# fretscanner5000.net
KiCad netlist of a schematic drawn in EAGLE
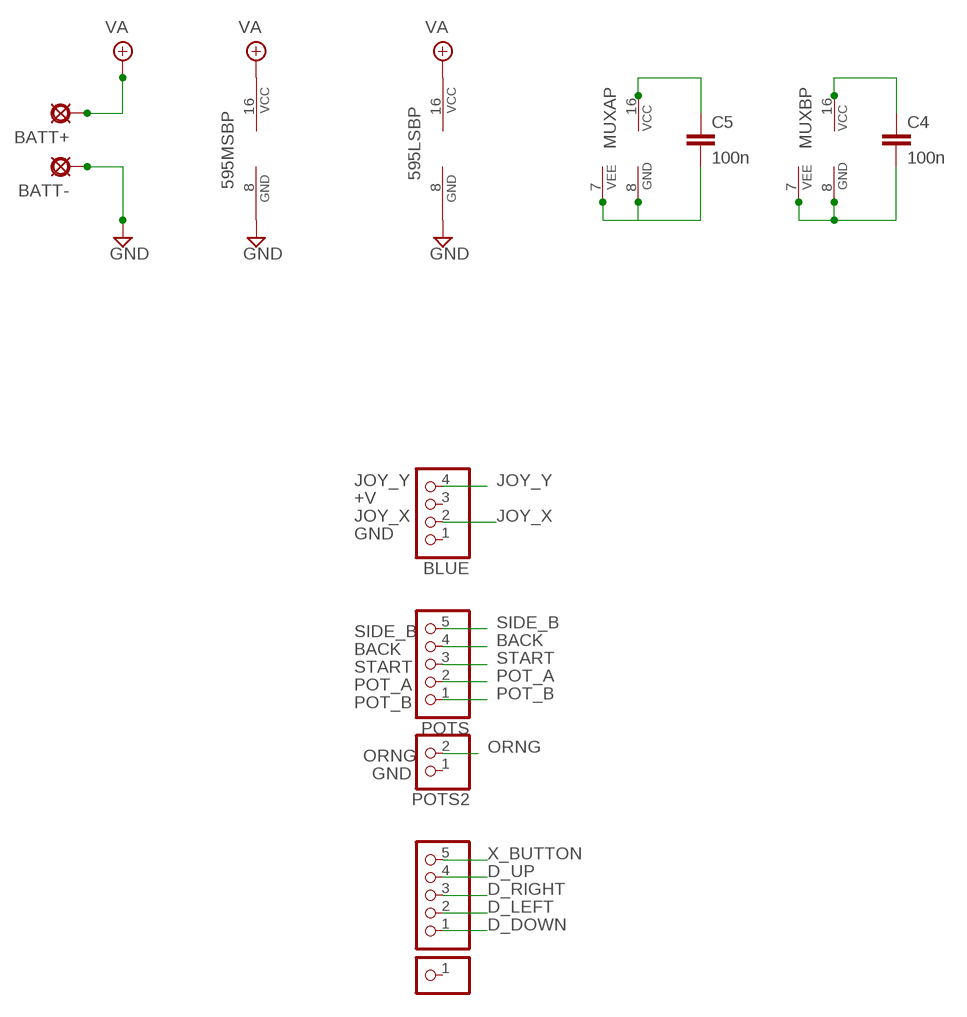
[diagram p0: schematic, sheet 1, part 1 of 2]
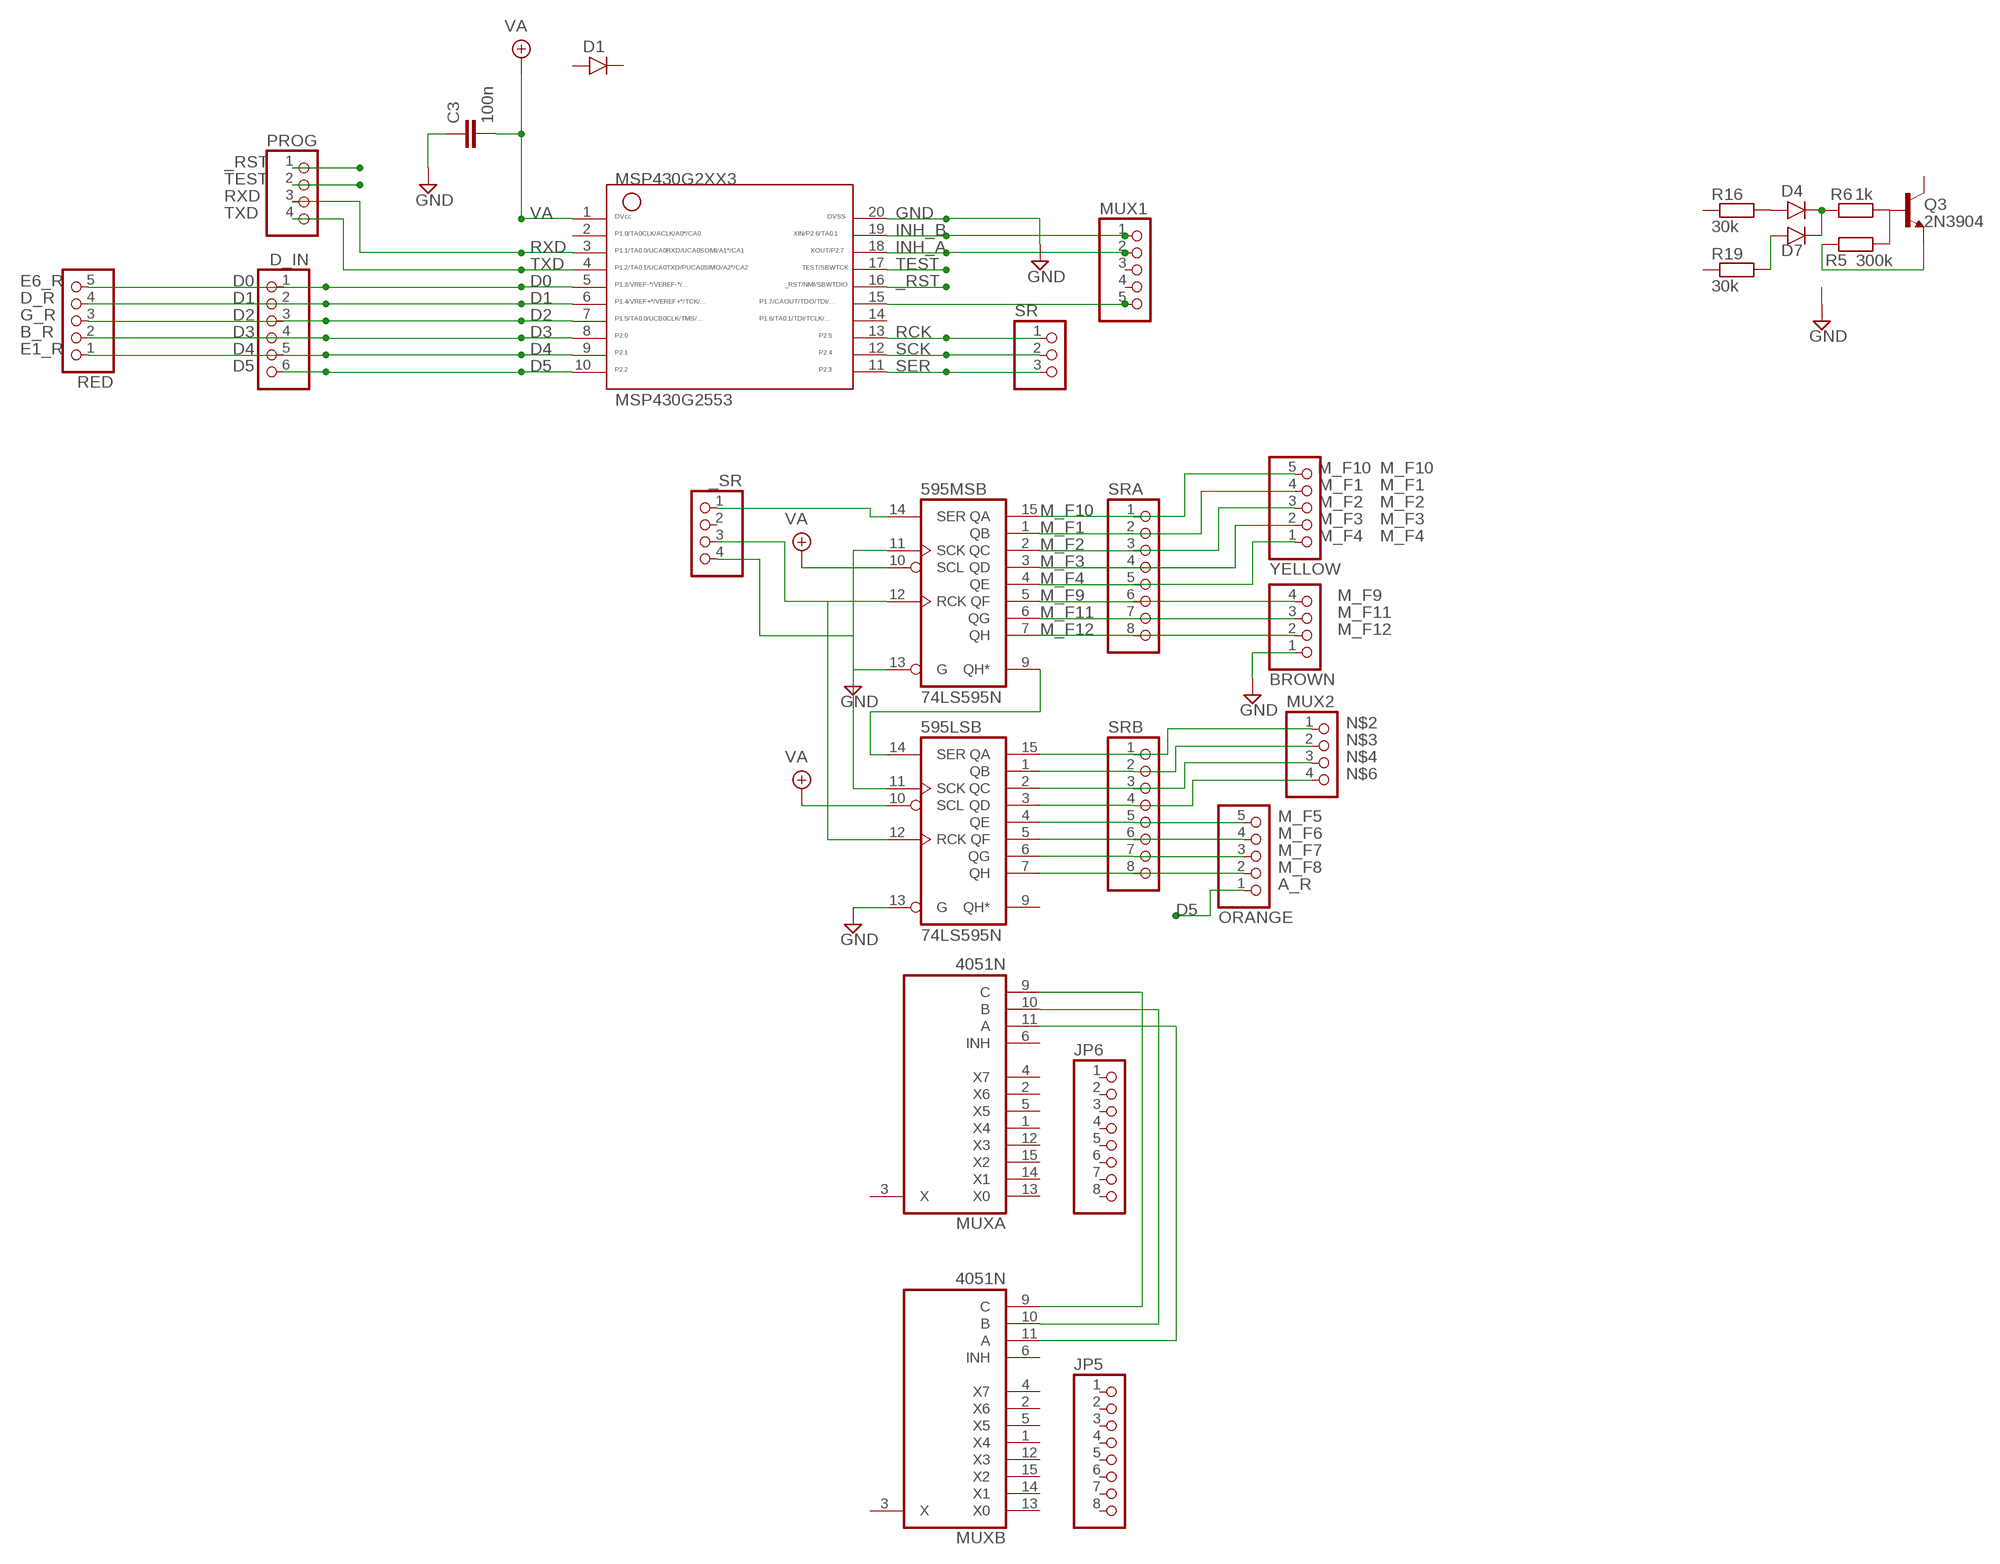
[diagram p1: schematic, sheet 1, part 2 of 2]

(export (version "E")
  (design (tool "Eeschema 10.0.6"))
  (components
    (comp (ref "595LSB")
      (value "74LS595N")
      (footprint "eagle-import:DIL16")
      (libsource (lib "eagle-import") (part "74595NLS"))
    )
    (comp (ref "595MSB")
      (value "74LS595N")
      (footprint "eagle-import:DIL16")
      (libsource (lib "eagle-import") (part "74595NLS"))
    )
    (comp (ref "BATT+")
      (value "PADL")
      (footprint "eagle-import:LONG")
      (libsource (lib "eagle-import") (part "PADL"))
    )
    (comp (ref "BATT-")
      (value "PADL")
      (footprint "eagle-import:LONG")
      (libsource (lib "eagle-import") (part "PADL"))
    )
    (comp (ref "BLUE")
      (value "PINHD-1X4")
      (footprint "eagle-import:1X04")
      (libsource (lib "eagle-import") (part "PINHD-1X4"))
    )
    (comp (ref "BROWN")
      (value "PINHD-1X4")
      (footprint "eagle-import:1X04")
      (libsource (lib "eagle-import") (part "PINHD-1X4"))
    )
    (comp (ref "C3")
      (value "100n")
      (footprint "eagle-import:050X030_050_3")
      (libsource (lib "eagle-import") (part "050X030_050"))
    )
    (comp (ref "C4")
      (value "100n")
      (footprint "eagle-import:050X030_050_3")
      (libsource (lib "eagle-import") (part "050X030_050"))
    )
    (comp (ref "C5")
      (value "100n")
      (footprint "eagle-import:050X030_050_3")
      (libsource (lib "eagle-import") (part "050X030_050"))
    )
    (comp (ref "D1")
      (value "1N400X.4")
      (footprint "eagle-import:DO41-4")
      (libsource (lib "eagle-import") (part "1N400X.4"))
    )
    (comp (ref "D4")
      (value "1N4148-2")
      (footprint "eagle-import:DO35-2")
      (libsource (lib "eagle-import") (part "1N4148-2"))
    )
    (comp (ref "D7")
      (value "1N4148-2")
      (footprint "eagle-import:DO35-2")
      (libsource (lib "eagle-import") (part "1N4148-2"))
    )
    (comp (ref "DPAD")
      (value "PINHD-1X5")
      (footprint "eagle-import:1X05")
      (libsource (lib "eagle-import") (part "PINHD-1X5"))
    )
    (comp (ref "DPAD2")
      (value "PINHD-1X1")
      (footprint "eagle-import:1X01")
      (libsource (lib "eagle-import") (part "PINHD-1X1"))
    )
    (comp (ref "D_IN")
      (value "PINHD-1X6")
      (footprint "eagle-import:1X06")
      (libsource (lib "eagle-import") (part "PINHD-1X6"))
    )
    (comp (ref "JP5")
      (value "PINHD-1X8")
      (footprint "eagle-import:1X08")
      (libsource (lib "eagle-import") (part "PINHD-1X8"))
    )
    (comp (ref "JP6")
      (value "PINHD-1X8")
      (footprint "eagle-import:1X08")
      (libsource (lib "eagle-import") (part "PINHD-1X8"))
    )
    (comp (ref "MSP430G2553")
      (value "G2XX3---N20")
      (footprint "eagle-import:N20")
      (libsource (lib "eagle-import") (part "G2XX3---N20"))
    )
    (comp (ref "MUX1")
      (value "PINHD-1X5")
      (footprint "eagle-import:1X05")
      (libsource (lib "eagle-import") (part "PINHD-1X5"))
    )
    (comp (ref "MUX2")
      (value "PINHD-1X4")
      (footprint "eagle-import:1X04")
      (libsource (lib "eagle-import") (part "PINHD-1X4"))
    )
    (comp (ref "MUXA")
      (value "4051N")
      (footprint "eagle-import:DIL16")
      (libsource (lib "eagle-import") (part "4051N"))
    )
    (comp (ref "MUXB")
      (value "4051N")
      (footprint "eagle-import:DIL16")
      (libsource (lib "eagle-import") (part "4051N"))
    )
    (comp (ref "ORANGE")
      (value "PINHD-1X5")
      (footprint "eagle-import:1X05")
      (libsource (lib "eagle-import") (part "PINHD-1X5"))
    )
    (comp (ref "POTS")
      (value "PINHD-1X5")
      (footprint "eagle-import:1X05")
      (libsource (lib "eagle-import") (part "PINHD-1X5"))
    )
    (comp (ref "POTS2")
      (value "PINHD-1X2")
      (footprint "eagle-import:1X02")
      (libsource (lib "eagle-import") (part "PINHD-1X2"))
    )
    (comp (ref "PROG")
      (value "PINHD-1X4")
      (footprint "eagle-import:1X04")
      (libsource (lib "eagle-import") (part "PINHD-1X4"))
    )
    (comp (ref "Q3")
      (value "2N3904")
      (footprint "eagle-import:TO92-")
      (libsource (lib "eagle-import") (part "2N3904"))
    )
    (comp (ref "R5")
      (value "300k")
      (footprint "eagle-import:R0207_1V")
      (libsource (lib "eagle-import") (part "6MM-EU1"))
    )
    (comp (ref "R6")
      (value "1k")
      (footprint "eagle-import:R0207_3")
      (libsource (lib "eagle-import") (part "6MM-EU"))
    )
    (comp (ref "R16")
      (value "30k")
      (footprint "eagle-import:R0207_3")
      (libsource (lib "eagle-import") (part "6MM-EU"))
    )
    (comp (ref "R19")
      (value "30k")
      (footprint "eagle-import:R0207_3")
      (libsource (lib "eagle-import") (part "6MM-EU"))
    )
    (comp (ref "RED")
      (value "PINHD-1X5")
      (footprint "eagle-import:1X05")
      (libsource (lib "eagle-import") (part "PINHD-1X5"))
    )
    (comp (ref "SR")
      (value "PINHD-1X3")
      (footprint "eagle-import:1X03")
      (libsource (lib "eagle-import") (part "PINHD-1X3"))
    )
    (comp (ref "SRA")
      (value "PINHD-1X8")
      (footprint "eagle-import:1X08")
      (libsource (lib "eagle-import") (part "PINHD-1X8"))
    )
    (comp (ref "SRB")
      (value "PINHD-1X8")
      (footprint "eagle-import:1X08")
      (libsource (lib "eagle-import") (part "PINHD-1X8"))
    )
    (comp (ref "YELLOW")
      (value "PINHD-1X5")
      (footprint "eagle-import:1X05")
      (libsource (lib "eagle-import") (part "PINHD-1X5"))
    )
    (comp (ref "_SR")
      (value "PINHD-1X4")
      (footprint "eagle-import:1X04")
      (libsource (lib "eagle-import") (part "PINHD-1X4"))
    )
  )
  (nets
    (net (code "1") (name "/BACK") (class "Default")
      (node (ref "POTS") (pin "4") (pinfunction "4_4") (pintype "passive"))
    )
    (net (code "2") (name "/D0") (class "Default")
      (node (ref "D_IN") (pin "1") (pinfunction "1_1") (pintype "passive"))
      (node (ref "MSP430G2553") (pin "5") (pinfunction "5_5") (pintype "bidirectional"))
      (node (ref "RED") (pin "5") (pinfunction "5_5") (pintype "passive"))
    )
    (net (code "3") (name "/D1") (class "Default")
      (node (ref "D_IN") (pin "2") (pinfunction "2_2") (pintype "passive"))
      (node (ref "MSP430G2553") (pin "6") (pinfunction "6_6") (pintype "bidirectional"))
      (node (ref "RED") (pin "4") (pinfunction "4_4") (pintype "passive"))
    )
    (net (code "4") (name "/D2") (class "Default")
      (node (ref "D_IN") (pin "3") (pinfunction "3_3") (pintype "passive"))
      (node (ref "MSP430G2553") (pin "7") (pinfunction "7_7") (pintype "bidirectional"))
      (node (ref "RED") (pin "3") (pinfunction "3_3") (pintype "passive"))
    )
    (net (code "5") (name "/D3") (class "Default")
      (node (ref "D_IN") (pin "4") (pinfunction "4_4") (pintype "passive"))
      (node (ref "MSP430G2553") (pin "8") (pinfunction "8_8") (pintype "bidirectional"))
      (node (ref "RED") (pin "2") (pinfunction "2_2") (pintype "passive"))
    )
    (net (code "6") (name "/D4") (class "Default")
      (node (ref "D_IN") (pin "5") (pinfunction "5_5") (pintype "passive"))
      (node (ref "MSP430G2553") (pin "9") (pinfunction "9_9") (pintype "bidirectional"))
      (node (ref "RED") (pin "1") (pinfunction "1_1") (pintype "passive"))
    )
    (net (code "7") (name "/D5") (class "Default")
      (node (ref "D_IN") (pin "6") (pinfunction "6_6") (pintype "passive"))
      (node (ref "MSP430G2553") (pin "10") (pinfunction "10_10") (pintype "bidirectional"))
      (node (ref "ORANGE") (pin "1") (pinfunction "1_1") (pintype "passive"))
    )
    (net (code "8") (name "/D_DOWN") (class "Default")
      (node (ref "DPAD") (pin "1") (pinfunction "1_1") (pintype "passive"))
    )
    (net (code "9") (name "/D_LEFT") (class "Default")
      (node (ref "DPAD") (pin "2") (pinfunction "2_2") (pintype "passive"))
    )
    (net (code "10") (name "/D_RIGHT") (class "Default")
      (node (ref "DPAD") (pin "3") (pinfunction "3_3") (pintype "passive"))
    )
    (net (code "11") (name "/D_UP") (class "Default")
      (node (ref "DPAD") (pin "4") (pinfunction "4_4") (pintype "passive"))
    )
    (net (code "12") (name "/INH_A") (class "Default")
      (node (ref "MSP430G2553") (pin "18") (pinfunction "18_18") (pintype "bidirectional"))
      (node (ref "MUX1") (pin "2") (pinfunction "2_2") (pintype "passive"))
    )
    (net (code "13") (name "/INH_B") (class "Default")
      (node (ref "MSP430G2553") (pin "19") (pinfunction "19_19") (pintype "bidirectional"))
      (node (ref "MUX1") (pin "1") (pinfunction "1_1") (pintype "passive"))
    )
    (net (code "14") (name "/JOY_X") (class "Default")
      (node (ref "BLUE") (pin "2") (pinfunction "2_2") (pintype "passive"))
    )
    (net (code "15") (name "/JOY_Y") (class "Default")
      (node (ref "BLUE") (pin "4") (pinfunction "4_4") (pintype "passive"))
    )
    (net (code "16") (name "/M_F1") (class "Default")
      (node (ref "595MSB") (pin "1") (pinfunction "QB_1") (pintype "tri_state"))
      (node (ref "SRA") (pin "2") (pinfunction "2_2") (pintype "passive"))
      (node (ref "YELLOW") (pin "4") (pinfunction "4_4") (pintype "passive"))
    )
    (net (code "17") (name "/M_F2") (class "Default")
      (node (ref "595MSB") (pin "2") (pinfunction "QC_2") (pintype "tri_state"))
      (node (ref "SRA") (pin "3") (pinfunction "3_3") (pintype "passive"))
      (node (ref "YELLOW") (pin "3") (pinfunction "3_3") (pintype "passive"))
    )
    (net (code "18") (name "/M_F3") (class "Default")
      (node (ref "595MSB") (pin "3") (pinfunction "QD_3") (pintype "tri_state"))
      (node (ref "SRA") (pin "4") (pinfunction "4_4") (pintype "passive"))
      (node (ref "YELLOW") (pin "2") (pinfunction "2_2") (pintype "passive"))
    )
    (net (code "19") (name "/M_F4") (class "Default")
      (node (ref "595MSB") (pin "4") (pinfunction "QE_4") (pintype "tri_state"))
      (node (ref "SRA") (pin "5") (pinfunction "5_5") (pintype "passive"))
      (node (ref "YELLOW") (pin "1") (pinfunction "1_1") (pintype "passive"))
    )
    (net (code "20") (name "/M_F5") (class "Default")
      (node (ref "595LSB") (pin "4") (pinfunction "QE_4") (pintype "tri_state"))
      (node (ref "ORANGE") (pin "5") (pinfunction "5_5") (pintype "passive"))
      (node (ref "SRB") (pin "5") (pinfunction "5_5") (pintype "passive"))
    )
    (net (code "21") (name "/M_F6") (class "Default")
      (node (ref "595LSB") (pin "5") (pinfunction "QF_5") (pintype "tri_state"))
      (node (ref "ORANGE") (pin "4") (pinfunction "4_4") (pintype "passive"))
      (node (ref "SRB") (pin "6") (pinfunction "6_6") (pintype "passive"))
    )
    (net (code "22") (name "/M_F7") (class "Default")
      (node (ref "595LSB") (pin "6") (pinfunction "QG_6") (pintype "tri_state"))
      (node (ref "ORANGE") (pin "3") (pinfunction "3_3") (pintype "passive"))
      (node (ref "SRB") (pin "7") (pinfunction "7_7") (pintype "passive"))
    )
    (net (code "23") (name "/M_F8") (class "Default")
      (node (ref "595LSB") (pin "7") (pinfunction "QH_7") (pintype "tri_state"))
      (node (ref "ORANGE") (pin "2") (pinfunction "2_2") (pintype "passive"))
      (node (ref "SRB") (pin "8") (pinfunction "8_8") (pintype "passive"))
    )
    (net (code "24") (name "/M_F9") (class "Default")
      (node (ref "595MSB") (pin "5") (pinfunction "QF_5") (pintype "tri_state"))
      (node (ref "BROWN") (pin "4") (pinfunction "4_4") (pintype "passive"))
      (node (ref "SRA") (pin "6") (pinfunction "6_6") (pintype "passive"))
    )
    (net (code "25") (name "/M_F10") (class "Default")
      (node (ref "595MSB") (pin "15") (pinfunction "QA_15") (pintype "tri_state"))
      (node (ref "SRA") (pin "1") (pinfunction "1_1") (pintype "passive"))
      (node (ref "YELLOW") (pin "5") (pinfunction "5_5") (pintype "passive"))
    )
    (net (code "26") (name "/M_F11") (class "Default")
      (node (ref "595MSB") (pin "6") (pinfunction "QG_6") (pintype "tri_state"))
      (node (ref "BROWN") (pin "3") (pinfunction "3_3") (pintype "passive"))
      (node (ref "SRA") (pin "7") (pinfunction "7_7") (pintype "passive"))
    )
    (net (code "27") (name "/M_F12") (class "Default")
      (node (ref "595MSB") (pin "7") (pinfunction "QH_7") (pintype "tri_state"))
      (node (ref "BROWN") (pin "2") (pinfunction "2_2") (pintype "passive"))
      (node (ref "SRA") (pin "8") (pinfunction "8_8") (pintype "passive"))
    )
    (net (code "28") (name "/N$2") (class "Default")
      (node (ref "595LSB") (pin "15") (pinfunction "QA_15") (pintype "tri_state"))
      (node (ref "MUX2") (pin "1") (pinfunction "1_1") (pintype "passive"))
      (node (ref "SRB") (pin "1") (pinfunction "1_1") (pintype "passive"))
    )
    (net (code "29") (name "/N$3") (class "Default")
      (node (ref "595LSB") (pin "1") (pinfunction "QB_1") (pintype "tri_state"))
      (node (ref "MUX2") (pin "2") (pinfunction "2_2") (pintype "passive"))
      (node (ref "SRB") (pin "2") (pinfunction "2_2") (pintype "passive"))
    )
    (net (code "30") (name "/N$4") (class "Default")
      (node (ref "595LSB") (pin "2") (pinfunction "QC_2") (pintype "tri_state"))
      (node (ref "MUX2") (pin "3") (pinfunction "3_3") (pintype "passive"))
      (node (ref "SRB") (pin "3") (pinfunction "3_3") (pintype "passive"))
    )
    (net (code "31") (name "/N$6") (class "Default")
      (node (ref "595LSB") (pin "3") (pinfunction "QD_3") (pintype "tri_state"))
      (node (ref "MUX2") (pin "4") (pinfunction "4_4") (pintype "passive"))
      (node (ref "SRB") (pin "4") (pinfunction "4_4") (pintype "passive"))
    )
    (net (code "32") (name "/ORNG") (class "Default")
      (node (ref "POTS2") (pin "2") (pinfunction "2_2") (pintype "passive"))
    )
    (net (code "33") (name "/POT_A") (class "Default")
      (node (ref "POTS") (pin "2") (pinfunction "2_2") (pintype "passive"))
    )
    (net (code "34") (name "/POT_B") (class "Default")
      (node (ref "POTS") (pin "1") (pinfunction "1_1") (pintype "passive"))
    )
    (net (code "35") (name "/RCK") (class "Default")
      (node (ref "MSP430G2553") (pin "13") (pinfunction "13_13") (pintype "bidirectional"))
      (node (ref "SR") (pin "1") (pinfunction "1_1") (pintype "passive"))
    )
    (net (code "36") (name "/RXD") (class "Default")
      (node (ref "MSP430G2553") (pin "3") (pinfunction "3_3") (pintype "bidirectional"))
      (node (ref "PROG") (pin "3") (pinfunction "3_3") (pintype "passive"))
    )
    (net (code "37") (name "/SCK") (class "Default")
      (node (ref "MSP430G2553") (pin "12") (pinfunction "12_12") (pintype "bidirectional"))
      (node (ref "SR") (pin "2") (pinfunction "2_2") (pintype "passive"))
    )
    (net (code "38") (name "/SER") (class "Default")
      (node (ref "MSP430G2553") (pin "11") (pinfunction "11_11") (pintype "bidirectional"))
      (node (ref "SR") (pin "3") (pinfunction "3_3") (pintype "passive"))
    )
    (net (code "39") (name "/SIDE_B") (class "Default")
      (node (ref "POTS") (pin "5") (pinfunction "5_5") (pintype "passive"))
    )
    (net (code "40") (name "/START") (class "Default")
      (node (ref "POTS") (pin "3") (pinfunction "3_3") (pintype "passive"))
    )
    (net (code "41") (name "/TEST") (class "Default")
      (node (ref "MSP430G2553") (pin "17") (pinfunction "17_17") (pintype "bidirectional"))
      (node (ref "PROG") (pin "2") (pinfunction "2_2") (pintype "passive"))
    )
    (net (code "42") (name "/TXD") (class "Default")
      (node (ref "MSP430G2553") (pin "4") (pinfunction "4_4") (pintype "bidirectional"))
      (node (ref "PROG") (pin "4") (pinfunction "4_4") (pintype "passive"))
    )
    (net (code "43") (name "/X_BUTTON") (class "Default")
      (node (ref "DPAD") (pin "5") (pinfunction "5_5") (pintype "passive"))
    )
    (net (code "44") (name "/_RST") (class "Default")
      (node (ref "MSP430G2553") (pin "16") (pinfunction "16_16") (pintype "bidirectional"))
      (node (ref "PROG") (pin "1") (pinfunction "1_1") (pintype "passive"))
    )
    (net (code "45") (name "GND") (class "Default")
      (node (ref "595LSB") (pin "13") (pinfunction "G_13") (pintype "input"))
      (node (ref "595LSB") (pin "8") (pinfunction "GND_8") (pintype "power_in"))
      (node (ref "595MSB") (pin "13") (pinfunction "G_13") (pintype "input"))
      (node (ref "595MSB") (pin "8") (pinfunction "GND_8") (pintype "power_in"))
      (node (ref "BATT-") (pin "1") (pinfunction "PAD_1") (pintype "passive"))
      (node (ref "BROWN") (pin "1") (pinfunction "1_1") (pintype "passive"))
      (node (ref "C3") (pin "1") (pinfunction "1_1") (pintype "passive"))
      (node (ref "MSP430G2553") (pin "20") (pinfunction "20_20") (pintype "bidirectional"))
    )
    (net (code "46") (name "Net-(595LSBA-RCK)") (class "Default")
      (node (ref "595LSB") (pin "12") (pinfunction "RCK_12") (pintype "input"))
      (node (ref "595MSB") (pin "12") (pinfunction "RCK_12") (pintype "input"))
      (node (ref "_SR") (pin "3") (pinfunction "3_3") (pintype "passive"))
    )
    (net (code "47") (name "Net-(595LSBA-SCK)") (class "Default")
      (node (ref "595LSB") (pin "11") (pinfunction "SCK_11") (pintype "input"))
      (node (ref "595MSB") (pin "11") (pinfunction "SCK_11") (pintype "input"))
      (node (ref "_SR") (pin "4") (pinfunction "4_4") (pintype "passive"))
    )
    (net (code "48") (name "Net-(595LSBA-SER)") (class "Default")
      (node (ref "595LSB") (pin "14") (pinfunction "SER_14") (pintype "input"))
      (node (ref "595MSB") (pin "9") (pinfunction "QH*_9") (pintype "tri_state"))
    )
    (net (code "49") (name "Net-(595MSBA-SER)") (class "Default")
      (node (ref "595MSB") (pin "14") (pinfunction "SER_14") (pintype "input"))
      (node (ref "_SR") (pin "1") (pinfunction "1_1") (pintype "passive"))
    )
    (net (code "50") (name "Net-(D4-PadA)") (class "Default")
      (node (ref "D4") (pin "A") (pinfunction "A_A") (pintype "passive"))
      (node (ref "R16") (pin "2") (pinfunction "2_2") (pintype "passive"))
    )
    (net (code "51") (name "Net-(D4-PadC)") (class "Default")
      (node (ref "D4") (pin "C") (pinfunction "C_C") (pintype "passive"))
      (node (ref "D7") (pin "C") (pinfunction "C_C") (pintype "passive"))
      (node (ref "R6") (pin "1") (pinfunction "1_1") (pintype "passive"))
    )
    (net (code "52") (name "Net-(D7-PadA)") (class "Default")
      (node (ref "D7") (pin "A") (pinfunction "A_A") (pintype "passive"))
      (node (ref "R19") (pin "2") (pinfunction "2_2") (pintype "passive"))
    )
    (net (code "53") (name "Net-(MSP430G2553-Pad15)") (class "Default")
      (node (ref "MSP430G2553") (pin "15") (pinfunction "15_15") (pintype "bidirectional"))
      (node (ref "MUX1") (pin "5") (pinfunction "5_5") (pintype "passive"))
    )
    (net (code "54") (name "Net-(MUXAA-A)") (class "Default")
      (node (ref "MUXA") (pin "11") (pinfunction "A_11") (pintype "input"))
      (node (ref "MUXB") (pin "11") (pinfunction "A_11") (pintype "input"))
    )
    (net (code "55") (name "Net-(MUXAA-B)") (class "Default")
      (node (ref "MUXA") (pin "10") (pinfunction "B_10") (pintype "input"))
      (node (ref "MUXB") (pin "10") (pinfunction "B_10") (pintype "input"))
    )
    (net (code "56") (name "Net-(MUXAA-C)") (class "Default")
      (node (ref "MUXA") (pin "9") (pinfunction "C_9") (pintype "input"))
      (node (ref "MUXB") (pin "9") (pinfunction "C_9") (pintype "input"))
    )
    (net (code "57") (name "Net-(MUXAB-GND)") (class "Default")
      (node (ref "C5") (pin "2") (pinfunction "2_2") (pintype "passive"))
      (node (ref "MUXA") (pin "7") (pinfunction "VEE_7") (pintype "power_in"))
      (node (ref "MUXA") (pin "8") (pinfunction "GND_8") (pintype "power_in"))
    )
    (net (code "58") (name "Net-(MUXAB-VCC)") (class "Default")
      (node (ref "C5") (pin "1") (pinfunction "1_1") (pintype "passive"))
      (node (ref "MUXA") (pin "16") (pinfunction "VCC_16") (pintype "power_in"))
    )
    (net (code "59") (name "Net-(MUXBB-GND)") (class "Default")
      (node (ref "C4") (pin "2") (pinfunction "2_2") (pintype "passive"))
      (node (ref "MUXB") (pin "7") (pinfunction "VEE_7") (pintype "power_in"))
      (node (ref "MUXB") (pin "8") (pinfunction "GND_8") (pintype "power_in"))
    )
    (net (code "60") (name "Net-(MUXBB-VCC)") (class "Default")
      (node (ref "C4") (pin "1") (pinfunction "1_1") (pintype "passive"))
      (node (ref "MUXB") (pin "16") (pinfunction "VCC_16") (pintype "power_in"))
    )
    (net (code "61") (name "Net-(Q3-B)") (class "Default")
      (node (ref "Q3") (pin "2") (pinfunction "B_2") (pintype "passive"))
      (node (ref "R5") (pin "1") (pinfunction "1_1") (pintype "passive"))
      (node (ref "R6") (pin "2") (pinfunction "2_2") (pintype "passive"))
    )
    (net (code "62") (name "Net-(Q3-E)") (class "Default")
      (node (ref "Q3") (pin "3") (pinfunction "E_3") (pintype "passive"))
      (node (ref "R5") (pin "2") (pinfunction "2_2") (pintype "passive"))
    )
    (net (code "63") (name "VA") (class "Default")
      (node (ref "595LSB") (pin "10") (pinfunction "SCL_10") (pintype "input"))
      (node (ref "595LSB") (pin "16") (pinfunction "VCC_16") (pintype "power_in"))
      (node (ref "595MSB") (pin "10") (pinfunction "SCL_10") (pintype "input"))
      (node (ref "595MSB") (pin "16") (pinfunction "VCC_16") (pintype "power_in"))
      (node (ref "BATT+") (pin "1") (pinfunction "PAD_1") (pintype "passive"))
      (node (ref "C3") (pin "2") (pinfunction "2_2") (pintype "passive"))
      (node (ref "MSP430G2553") (pin "1") (pinfunction "1_1") (pintype "bidirectional"))
    )
    (net (code "64") (name "unconnected-(595LSBA-QH*-Pad9)") (class "Default")
      (node (ref "595LSB") (pin "9") (pinfunction "QH*_9") (pintype "tri_state"))
    )
    (net (code "65") (name "unconnected-(BLUE-Pad1)") (class "Default")
      (node (ref "BLUE") (pin "1") (pinfunction "1_1") (pintype "passive"))
    )
    (net (code "66") (name "unconnected-(BLUE-Pad3)") (class "Default")
      (node (ref "BLUE") (pin "3") (pinfunction "3_3") (pintype "passive"))
    )
    (net (code "67") (name "unconnected-(D1-PadA)") (class "Default")
      (node (ref "D1") (pin "A") (pinfunction "A_A") (pintype "passive"))
    )
    (net (code "68") (name "unconnected-(D1-PadC)") (class "Default")
      (node (ref "D1") (pin "C") (pinfunction "C_C") (pintype "passive"))
    )
    (net (code "69") (name "unconnected-(DPAD2-Pad1)") (class "Default")
      (node (ref "DPAD2") (pin "1") (pinfunction "1_1") (pintype "passive"))
    )
    (net (code "70") (name "unconnected-(JP5-Pad1)") (class "Default")
      (node (ref "JP5") (pin "1") (pinfunction "1_1") (pintype "passive"))
    )
    (net (code "71") (name "unconnected-(JP5-Pad2)") (class "Default")
      (node (ref "JP5") (pin "2") (pinfunction "2_2") (pintype "passive"))
    )
    (net (code "72") (name "unconnected-(JP5-Pad3)") (class "Default")
      (node (ref "JP5") (pin "3") (pinfunction "3_3") (pintype "passive"))
    )
    (net (code "73") (name "unconnected-(JP5-Pad4)") (class "Default")
      (node (ref "JP5") (pin "4") (pinfunction "4_4") (pintype "passive"))
    )
    (net (code "74") (name "unconnected-(JP5-Pad5)") (class "Default")
      (node (ref "JP5") (pin "5") (pinfunction "5_5") (pintype "passive"))
    )
    (net (code "75") (name "unconnected-(JP5-Pad6)") (class "Default")
      (node (ref "JP5") (pin "6") (pinfunction "6_6") (pintype "passive"))
    )
    (net (code "76") (name "unconnected-(JP5-Pad7)") (class "Default")
      (node (ref "JP5") (pin "7") (pinfunction "7_7") (pintype "passive"))
    )
    (net (code "77") (name "unconnected-(JP5-Pad8)") (class "Default")
      (node (ref "JP5") (pin "8") (pinfunction "8_8") (pintype "passive"))
    )
    (net (code "78") (name "unconnected-(JP6-Pad1)") (class "Default")
      (node (ref "JP6") (pin "1") (pinfunction "1_1") (pintype "passive"))
    )
    (net (code "79") (name "unconnected-(JP6-Pad2)") (class "Default")
      (node (ref "JP6") (pin "2") (pinfunction "2_2") (pintype "passive"))
    )
    (net (code "80") (name "unconnected-(JP6-Pad3)") (class "Default")
      (node (ref "JP6") (pin "3") (pinfunction "3_3") (pintype "passive"))
    )
    (net (code "81") (name "unconnected-(JP6-Pad4)") (class "Default")
      (node (ref "JP6") (pin "4") (pinfunction "4_4") (pintype "passive"))
    )
    (net (code "82") (name "unconnected-(JP6-Pad5)") (class "Default")
      (node (ref "JP6") (pin "5") (pinfunction "5_5") (pintype "passive"))
    )
    (net (code "83") (name "unconnected-(JP6-Pad6)") (class "Default")
      (node (ref "JP6") (pin "6") (pinfunction "6_6") (pintype "passive"))
    )
    (net (code "84") (name "unconnected-(JP6-Pad7)") (class "Default")
      (node (ref "JP6") (pin "7") (pinfunction "7_7") (pintype "passive"))
    )
    (net (code "85") (name "unconnected-(JP6-Pad8)") (class "Default")
      (node (ref "JP6") (pin "8") (pinfunction "8_8") (pintype "passive"))
    )
    (net (code "86") (name "unconnected-(MSP430G2553-Pad2)") (class "Default")
      (node (ref "MSP430G2553") (pin "2") (pinfunction "2_2") (pintype "bidirectional"))
    )
    (net (code "87") (name "unconnected-(MSP430G2553-Pad14)") (class "Default")
      (node (ref "MSP430G2553") (pin "14") (pinfunction "14_14") (pintype "bidirectional"))
    )
    (net (code "88") (name "unconnected-(MUX1-Pad3)") (class "Default")
      (node (ref "MUX1") (pin "3") (pinfunction "3_3") (pintype "passive"))
    )
    (net (code "89") (name "unconnected-(MUX1-Pad4)") (class "Default")
      (node (ref "MUX1") (pin "4") (pinfunction "4_4") (pintype "passive"))
    )
    (net (code "90") (name "unconnected-(MUXAA-INH-Pad6)") (class "Default")
      (node (ref "MUXA") (pin "6") (pinfunction "INH_6") (pintype "input"))
    )
    (net (code "91") (name "unconnected-(MUXAA-X-Pad3)") (class "Default")
      (node (ref "MUXA") (pin "3") (pinfunction "X_3") (pintype "bidirectional"))
    )
    (net (code "92") (name "unconnected-(MUXAA-X0-Pad13)") (class "Default")
      (node (ref "MUXA") (pin "13") (pinfunction "X0_13") (pintype "bidirectional"))
    )
    (net (code "93") (name "unconnected-(MUXAA-X1-Pad14)") (class "Default")
      (node (ref "MUXA") (pin "14") (pinfunction "X1_14") (pintype "bidirectional"))
    )
    (net (code "94") (name "unconnected-(MUXAA-X2-Pad15)") (class "Default")
      (node (ref "MUXA") (pin "15") (pinfunction "X2_15") (pintype "bidirectional"))
    )
    (net (code "95") (name "unconnected-(MUXAA-X3-Pad12)") (class "Default")
      (node (ref "MUXA") (pin "12") (pinfunction "X3_12") (pintype "bidirectional"))
    )
    (net (code "96") (name "unconnected-(MUXAA-X4-Pad1)") (class "Default")
      (node (ref "MUXA") (pin "1") (pinfunction "X4_1") (pintype "bidirectional"))
    )
    (net (code "97") (name "unconnected-(MUXAA-X5-Pad5)") (class "Default")
      (node (ref "MUXA") (pin "5") (pinfunction "X5_5") (pintype "bidirectional"))
    )
    (net (code "98") (name "unconnected-(MUXAA-X6-Pad2)") (class "Default")
      (node (ref "MUXA") (pin "2") (pinfunction "X6_2") (pintype "bidirectional"))
    )
    (net (code "99") (name "unconnected-(MUXAA-X7-Pad4)") (class "Default")
      (node (ref "MUXA") (pin "4") (pinfunction "X7_4") (pintype "bidirectional"))
    )
    (net (code "100") (name "unconnected-(MUXBA-INH-Pad6)") (class "Default")
      (node (ref "MUXB") (pin "6") (pinfunction "INH_6") (pintype "input"))
    )
    (net (code "101") (name "unconnected-(MUXBA-X-Pad3)") (class "Default")
      (node (ref "MUXB") (pin "3") (pinfunction "X_3") (pintype "bidirectional"))
    )
    (net (code "102") (name "unconnected-(MUXBA-X0-Pad13)") (class "Default")
      (node (ref "MUXB") (pin "13") (pinfunction "X0_13") (pintype "bidirectional"))
    )
    (net (code "103") (name "unconnected-(MUXBA-X1-Pad14)") (class "Default")
      (node (ref "MUXB") (pin "14") (pinfunction "X1_14") (pintype "bidirectional"))
    )
    (net (code "104") (name "unconnected-(MUXBA-X2-Pad15)") (class "Default")
      (node (ref "MUXB") (pin "15") (pinfunction "X2_15") (pintype "bidirectional"))
    )
    (net (code "105") (name "unconnected-(MUXBA-X3-Pad12)") (class "Default")
      (node (ref "MUXB") (pin "12") (pinfunction "X3_12") (pintype "bidirectional"))
    )
    (net (code "106") (name "unconnected-(MUXBA-X4-Pad1)") (class "Default")
      (node (ref "MUXB") (pin "1") (pinfunction "X4_1") (pintype "bidirectional"))
    )
    (net (code "107") (name "unconnected-(MUXBA-X5-Pad5)") (class "Default")
      (node (ref "MUXB") (pin "5") (pinfunction "X5_5") (pintype "bidirectional"))
    )
    (net (code "108") (name "unconnected-(MUXBA-X6-Pad2)") (class "Default")
      (node (ref "MUXB") (pin "2") (pinfunction "X6_2") (pintype "bidirectional"))
    )
    (net (code "109") (name "unconnected-(MUXBA-X7-Pad4)") (class "Default")
      (node (ref "MUXB") (pin "4") (pinfunction "X7_4") (pintype "bidirectional"))
    )
    (net (code "110") (name "unconnected-(POTS2-Pad1)") (class "Default")
      (node (ref "POTS2") (pin "1") (pinfunction "1_1") (pintype "passive"))
    )
    (net (code "111") (name "unconnected-(Q3-C-Pad1)") (class "Default")
      (node (ref "Q3") (pin "1") (pinfunction "C_1") (pintype "passive"))
    )
    (net (code "112") (name "unconnected-(R16-Pad1)") (class "Default")
      (node (ref "R16") (pin "1") (pinfunction "1_1") (pintype "passive"))
    )
    (net (code "113") (name "unconnected-(R19-Pad1)") (class "Default")
      (node (ref "R19") (pin "1") (pinfunction "1_1") (pintype "passive"))
    )
    (net (code "114") (name "unconnected-(_SR-Pad2)") (class "Default")
      (node (ref "_SR") (pin "2") (pinfunction "2_2") (pintype "passive"))
    )
  )
)
